# Comms.net
KiCad netlist of a schematic drawn in Altium Designer
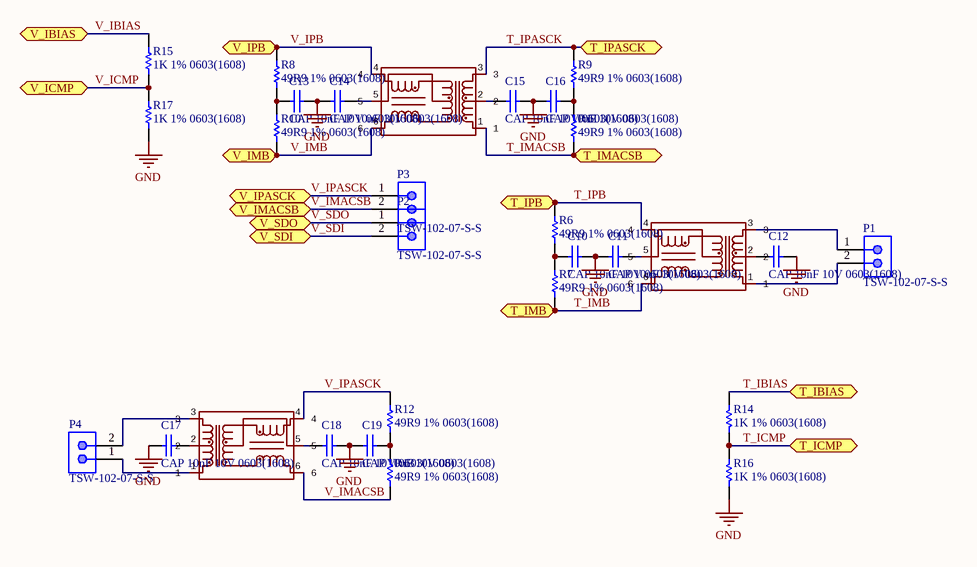
[diagram p0: Comms.SchDoc]

(export (version "E")
  (design (tool "Eeschema 10.0.6"))
  (components
    (comp (ref "4")
      (value "HM2108NL")
      (footprint "HM2108NL")
      (fields (field (name "LIBRARYNAME") "Transformers and Chokes"))
      (libsource (lib "Transformers and Chokes") (part "HM2108NL"))
    )
    (comp (ref "5")
      (value "HM2108NL")
      (footprint "HM2108NL")
      (fields (field (name "LIBRARYNAME") "Transformers and Chokes"))
      (libsource (lib "Transformers and Chokes") (part "HM2108NL"))
    )
    (comp (ref "6")
      (value "HM2108NL")
      (footprint "HM2108NL")
      (fields (field (name "LIBRARYNAME") "Transformers and Chokes"))
      (libsource (lib "Transformers and Chokes") (part "HM2108NL"))
    )
    (comp (ref "C10")
      (value "CAP 10nF 10V 0603(1608)")
      (footprint "CAPC0603(1608)100_M")
      (description "CAP 10nF 10V ±2% 0603 (1608 Metric) Thickness 1mm SMD")
      (fields (field (name "TOLERANCE") "Â±2%"))
      (libsource (lib "Altium Content Vault") (part "CAP"))
    )
    (comp (ref "C11")
      (value "CAP 10nF 10V 0603(1608)")
      (footprint "CAPC0603(1608)100_M")
      (description "CAP 10nF 10V ±2% 0603 (1608 Metric) Thickness 1mm SMD")
      (fields (field (name "TOLERANCE") "Â±2%"))
      (libsource (lib "Altium Content Vault") (part "CAP"))
    )
    (comp (ref "C12")
      (value "CAP 10nF 10V 0603(1608)")
      (footprint "CAPC0603(1608)100_M")
      (description "CAP 10nF 10V ±2% 0603 (1608 Metric) Thickness 1mm SMD")
      (fields (field (name "TOLERANCE") "Â±2%"))
      (libsource (lib "Altium Content Vault") (part "CAP"))
    )
    (comp (ref "C13")
      (value "CAP 10nF 10V 0603(1608)")
      (footprint "CAPC0603(1608)100_M")
      (description "CAP 10nF 10V ±2% 0603 (1608 Metric) Thickness 1mm SMD")
      (fields (field (name "TOLERANCE") "Â±2%"))
      (libsource (lib "Altium Content Vault") (part "CAP"))
    )
    (comp (ref "C14")
      (value "CAP 10nF 10V 0603(1608)")
      (footprint "CAPC0603(1608)100_M")
      (description "CAP 10nF 10V ±2% 0603 (1608 Metric) Thickness 1mm SMD")
      (fields (field (name "TOLERANCE") "Â±2%"))
      (libsource (lib "Altium Content Vault") (part "CAP"))
    )
    (comp (ref "C15")
      (value "CAP 10nF 10V 0603(1608)")
      (footprint "CAPC0603(1608)100_M")
      (description "CAP 10nF 10V ±2% 0603 (1608 Metric) Thickness 1mm SMD")
      (fields (field (name "TOLERANCE") "Â±2%"))
      (libsource (lib "Altium Content Vault") (part "CAP"))
    )
    (comp (ref "C16")
      (value "CAP 10nF 10V 0603(1608)")
      (footprint "CAPC0603(1608)100_M")
      (description "CAP 10nF 10V ±2% 0603 (1608 Metric) Thickness 1mm SMD")
      (fields (field (name "TOLERANCE") "Â±2%"))
      (libsource (lib "Altium Content Vault") (part "CAP"))
    )
    (comp (ref "C17")
      (value "CAP 10nF 10V 0603(1608)")
      (footprint "CAPC0603(1608)100_M")
      (description "CAP 10nF 10V ±2% 0603 (1608 Metric) Thickness 1mm SMD")
      (fields (field (name "TOLERANCE") "Â±2%"))
      (libsource (lib "Altium Content Vault") (part "CAP"))
    )
    (comp (ref "C18")
      (value "CAP 10nF 10V 0603(1608)")
      (footprint "CAPC0603(1608)100_M")
      (description "CAP 10nF 10V ±2% 0603 (1608 Metric) Thickness 1mm SMD")
      (fields (field (name "TOLERANCE") "Â±2%"))
      (libsource (lib "Altium Content Vault") (part "CAP"))
    )
    (comp (ref "C19")
      (value "CAP 10nF 10V 0603(1608)")
      (footprint "CAPC0603(1608)100_M")
      (description "CAP 10nF 10V ±2% 0603 (1608 Metric) Thickness 1mm SMD")
      (fields (field (name "TOLERANCE") "Â±2%"))
      (libsource (lib "Altium Content Vault") (part "CAP"))
    )
    (comp (ref "P1")
      (value "TSW-102-07-S-S")
      (footprint "SMTC-TSW-102-07-S-S")
      (libsource (lib "Altium Content Vault") (part "CN-1P-M-R2"))
    )
    (comp (ref "P2")
      (value "TSW-102-07-S-S")
      (footprint "SMTC-TSW-102-07-S-S")
      (fields (field (name "MANUFACTURER") "Samtec"))
      (libsource (lib "Altium Content Vault") (part "CN-1P-M-R2"))
    )
    (comp (ref "P3")
      (value "TSW-102-07-S-S")
      (footprint "SMTC-TSW-102-07-S-S")
      (libsource (lib "Altium Content Vault") (part "CN-1P-M-R2"))
    )
    (comp (ref "P4")
      (value "TSW-102-07-S-S")
      (footprint "SMTC-TSW-102-07-S-S")
      (fields (field (name "MANUFACTURER") "Samtec"))
      (libsource (lib "") (part "CN-1P-M-R2_1"))
    )
    (comp (ref "R6")
      (value "49R9 1% 0603(1608)")
      (footprint "RESC0603(1608)_N")
      (description "49R9 0.1W 1% 0603 (1608 Metric)  SMD")
      (fields (field (name "POWER") "0.1 W") (field (name "TOLERANCE") "1 %"))
      (libsource (lib "Altium Content Vault") (part "RES"))
    )
    (comp (ref "R7")
      (value "49R9 1% 0603(1608)")
      (footprint "RESC0603(1608)_N")
      (description "49R9 0.1W 1% 0603 (1608 Metric)  SMD")
      (fields (field (name "POWER") "0.1 W") (field (name "TOLERANCE") "1 %"))
      (libsource (lib "Altium Content Vault") (part "RES"))
    )
    (comp (ref "R8")
      (value "49R9 1% 0603(1608)")
      (footprint "RESC0603(1608)_N")
      (description "49R9 0.1W 1% 0603 (1608 Metric)  SMD")
      (fields (field (name "POWER") "0.1 W") (field (name "TOLERANCE") "1 %"))
      (libsource (lib "Altium Content Vault") (part "RES"))
    )
    (comp (ref "R9")
      (value "49R9 1% 0603(1608)")
      (footprint "RESC0603(1608)_N")
      (description "49R9 0.1W 1% 0603 (1608 Metric)  SMD")
      (fields (field (name "POWER") "0.1 W") (field (name "TOLERANCE") "1 %"))
      (libsource (lib "Altium Content Vault") (part "RES"))
    )
    (comp (ref "R10")
      (value "49R9 1% 0603(1608)")
      (footprint "RESC0603(1608)_N")
      (description "49R9 0.1W 1% 0603 (1608 Metric)  SMD")
      (fields (field (name "POWER") "0.1 W") (field (name "TOLERANCE") "1 %"))
      (libsource (lib "Altium Content Vault") (part "RES"))
    )
    (comp (ref "R11")
      (value "49R9 1% 0603(1608)")
      (footprint "RESC0603(1608)_N")
      (description "49R9 0.1W 1% 0603 (1608 Metric)  SMD")
      (fields (field (name "POWER") "0.1 W") (field (name "TOLERANCE") "1 %"))
      (libsource (lib "Altium Content Vault") (part "RES"))
    )
    (comp (ref "R12")
      (value "49R9 1% 0603(1608)")
      (footprint "RESC0603(1608)_N")
      (description "49R9 0.1W 1% 0603 (1608 Metric)  SMD")
      (fields (field (name "POWER") "0.1 W") (field (name "TOLERANCE") "1 %"))
      (libsource (lib "Altium Content Vault") (part "RES"))
    )
    (comp (ref "R13")
      (value "49R9 1% 0603(1608)")
      (footprint "RESC0603(1608)_N")
      (description "49R9 0.1W 1% 0603 (1608 Metric)  SMD")
      (fields (field (name "POWER") "0.1 W") (field (name "TOLERANCE") "1 %"))
      (libsource (lib "Altium Content Vault") (part "RES"))
    )
    (comp (ref "R14")
      (value "1K 1% 0603(1608)")
      (footprint "RESC0603(1608)_M")
      (description "1K 0.1W 1% 0603 (1608 Metric)  SMD")
      (fields (field (name "TOLERANCE") "1 %") (field (name "POWER") "0.1 W"))
      (libsource (lib "Altium Content Vault") (part "RES"))
    )
    (comp (ref "R15")
      (value "1K 1% 0603(1608)")
      (footprint "RESC0603(1608)_M")
      (description "1K 0.1W 1% 0603 (1608 Metric)  SMD")
      (fields (field (name "TOLERANCE") "1 %") (field (name "POWER") "0.1 W"))
      (libsource (lib "Altium Content Vault") (part "RES"))
    )
    (comp (ref "R16")
      (value "1K 1% 0603(1608)")
      (footprint "RESC0603(1608)_M")
      (description "1K 0.1W 1% 0603 (1608 Metric)  SMD")
      (fields (field (name "TOLERANCE") "1 %") (field (name "POWER") "0.1 W"))
      (libsource (lib "Altium Content Vault") (part "RES"))
    )
    (comp (ref "R17")
      (value "1K 1% 0603(1608)")
      (footprint "RESC0603(1608)_M")
      (description "1K 0.1W 1% 0603 (1608 Metric)  SMD")
      (fields (field (name "TOLERANCE") "1 %") (field (name "POWER") "0.1 W"))
      (libsource (lib "Altium Content Vault") (part "RES"))
    )
  )
  (nets
    (net (code "1") (name "/T_IBIAS") (class "Default")
      (node (ref "R14") (pin "2") (pinfunction "2_2") (pintype "passive"))
    )
    (net (code "2") (name "/T_ICMP") (class "Default")
      (node (ref "R14") (pin "1") (pinfunction "1_1") (pintype "passive"))
      (node (ref "R16") (pin "2") (pinfunction "2_2") (pintype "passive"))
    )
    (net (code "3") (name "/T_IMACSB") (class "Default")
      (node (ref "5") (pin "1") (pinfunction "1_1") (pintype "passive"))
      (node (ref "R11") (pin "1") (pinfunction "1_1") (pintype "passive"))
    )
    (net (code "4") (name "/T_IMB") (class "Default")
      (node (ref "4") (pin "6") (pinfunction "6_6") (pintype "passive"))
      (node (ref "R7") (pin "1") (pinfunction "1_1") (pintype "passive"))
    )
    (net (code "5") (name "/T_IPASCK") (class "Default")
      (node (ref "5") (pin "3") (pinfunction "3_3") (pintype "passive"))
      (node (ref "R9") (pin "2") (pinfunction "2_2") (pintype "passive"))
    )
    (net (code "6") (name "/T_IPB") (class "Default")
      (node (ref "4") (pin "4") (pinfunction "4_4") (pintype "passive"))
      (node (ref "R6") (pin "2") (pinfunction "2_2") (pintype "passive"))
    )
    (net (code "7") (name "/V_IBIAS") (class "Default")
      (node (ref "R15") (pin "2") (pinfunction "2_2") (pintype "passive"))
    )
    (net (code "8") (name "/V_ICMP") (class "Default")
      (node (ref "R15") (pin "1") (pinfunction "1_1") (pintype "passive"))
      (node (ref "R17") (pin "2") (pinfunction "2_2") (pintype "passive"))
    )
    (net (code "9") (name "/V_IMACSB") (class "Default")
      (node (ref "6") (pin "6") (pinfunction "6_6") (pintype "passive"))
      (node (ref "P3") (pin "2") (pinfunction "2_2") (pintype "passive"))
      (node (ref "R13") (pin "1") (pinfunction "1_1") (pintype "passive"))
    )
    (net (code "10") (name "/V_IMB") (class "Default")
      (node (ref "5") (pin "6") (pinfunction "6_6") (pintype "passive"))
      (node (ref "R10") (pin "1") (pinfunction "1_1") (pintype "passive"))
    )
    (net (code "11") (name "/V_IPASCK") (class "Default")
      (node (ref "6") (pin "4") (pinfunction "4_4") (pintype "passive"))
      (node (ref "P3") (pin "1") (pinfunction "1_1") (pintype "passive"))
      (node (ref "R12") (pin "2") (pinfunction "2_2") (pintype "passive"))
    )
    (net (code "12") (name "/V_IPB") (class "Default")
      (node (ref "5") (pin "4") (pinfunction "4_4") (pintype "passive"))
      (node (ref "R8") (pin "2") (pinfunction "2_2") (pintype "passive"))
    )
    (net (code "13") (name "/V_SDI") (class "Default")
      (node (ref "P2") (pin "2") (pinfunction "2_2") (pintype "passive"))
    )
    (net (code "14") (name "/V_SDO") (class "Default")
      (node (ref "P2") (pin "1") (pinfunction "1_1") (pintype "passive"))
    )
    (net (code "15") (name "GND") (class "Default")
      (node (ref "C10") (pin "2") (pinfunction "2_2") (pintype "passive"))
      (node (ref "C11") (pin "1") (pinfunction "1_1") (pintype "passive"))
      (node (ref "C12") (pin "2") (pinfunction "2_2") (pintype "passive"))
      (node (ref "C13") (pin "2") (pinfunction "2_2") (pintype "passive"))
      (node (ref "C14") (pin "1") (pinfunction "1_1") (pintype "passive"))
      (node (ref "C15") (pin "2") (pinfunction "2_2") (pintype "passive"))
      (node (ref "C16") (pin "1") (pinfunction "1_1") (pintype "passive"))
      (node (ref "C17") (pin "1") (pinfunction "1_1") (pintype "passive"))
      (node (ref "C18") (pin "2") (pinfunction "2_2") (pintype "passive"))
      (node (ref "C19") (pin "1") (pinfunction "1_1") (pintype "passive"))
      (node (ref "R16") (pin "1") (pinfunction "1_1") (pintype "passive"))
      (node (ref "R17") (pin "1") (pinfunction "1_1") (pintype "passive"))
    )
    (net (code "16") (name "Net-(4-Pad1)") (class "Default")
      (node (ref "4") (pin "1") (pinfunction "1_1") (pintype "passive"))
      (node (ref "P1") (pin "2") (pinfunction "2_2") (pintype "passive"))
    )
    (net (code "17") (name "Net-(4-Pad2)") (class "Default")
      (node (ref "4") (pin "2") (pinfunction "2_2") (pintype "passive"))
      (node (ref "C12") (pin "1") (pinfunction "1_1") (pintype "passive"))
    )
    (net (code "18") (name "Net-(4-Pad3)") (class "Default")
      (node (ref "4") (pin "3") (pinfunction "3_3") (pintype "passive"))
      (node (ref "P1") (pin "1") (pinfunction "1_1") (pintype "passive"))
    )
    (net (code "19") (name "Net-(4-Pad5)") (class "Default")
      (node (ref "4") (pin "5") (pinfunction "5_5") (pintype "passive"))
      (node (ref "C11") (pin "2") (pinfunction "2_2") (pintype "passive"))
    )
    (net (code "20") (name "Net-(5-Pad2)") (class "Default")
      (node (ref "5") (pin "2") (pinfunction "2_2") (pintype "passive"))
      (node (ref "C15") (pin "1") (pinfunction "1_1") (pintype "passive"))
    )
    (net (code "21") (name "Net-(5-Pad5)") (class "Default")
      (node (ref "5") (pin "5") (pinfunction "5_5") (pintype "passive"))
      (node (ref "C14") (pin "2") (pinfunction "2_2") (pintype "passive"))
    )
    (net (code "22") (name "Net-(6-Pad1)") (class "Default")
      (node (ref "6") (pin "1") (pinfunction "1_1") (pintype "passive"))
      (node (ref "P4") (pin "1") (pinfunction "1_1") (pintype "passive"))
    )
    (net (code "23") (name "Net-(6-Pad2)") (class "Default")
      (node (ref "6") (pin "2") (pinfunction "2_2") (pintype "passive"))
      (node (ref "C17") (pin "2") (pinfunction "2_2") (pintype "passive"))
    )
    (net (code "24") (name "Net-(6-Pad3)") (class "Default")
      (node (ref "6") (pin "3") (pinfunction "3_3") (pintype "passive"))
      (node (ref "P4") (pin "2") (pinfunction "2_2") (pintype "passive"))
    )
    (net (code "25") (name "Net-(6-Pad5)") (class "Default")
      (node (ref "6") (pin "5") (pinfunction "5_5") (pintype "passive"))
      (node (ref "C18") (pin "1") (pinfunction "1_1") (pintype "passive"))
    )
    (net (code "26") (name "Net-(C10-Pad1)") (class "Default")
      (node (ref "C10") (pin "1") (pinfunction "1_1") (pintype "passive"))
      (node (ref "R6") (pin "1") (pinfunction "1_1") (pintype "passive"))
      (node (ref "R7") (pin "2") (pinfunction "2_2") (pintype "passive"))
    )
    (net (code "27") (name "Net-(C13-Pad1)") (class "Default")
      (node (ref "C13") (pin "1") (pinfunction "1_1") (pintype "passive"))
      (node (ref "R10") (pin "2") (pinfunction "2_2") (pintype "passive"))
      (node (ref "R8") (pin "1") (pinfunction "1_1") (pintype "passive"))
    )
    (net (code "28") (name "Net-(C16-Pad2)") (class "Default")
      (node (ref "C16") (pin "2") (pinfunction "2_2") (pintype "passive"))
      (node (ref "R11") (pin "2") (pinfunction "2_2") (pintype "passive"))
      (node (ref "R9") (pin "1") (pinfunction "1_1") (pintype "passive"))
    )
    (net (code "29") (name "Net-(C19-Pad2)") (class "Default")
      (node (ref "C19") (pin "2") (pinfunction "2_2") (pintype "passive"))
      (node (ref "R12") (pin "1") (pinfunction "1_1") (pintype "passive"))
      (node (ref "R13") (pin "2") (pinfunction "2_2") (pintype "passive"))
    )
  )
)
